# rev-polarity-deflector-dish-mk-2_0.net
KiCad netlist of a schematic drawn in EAGLE
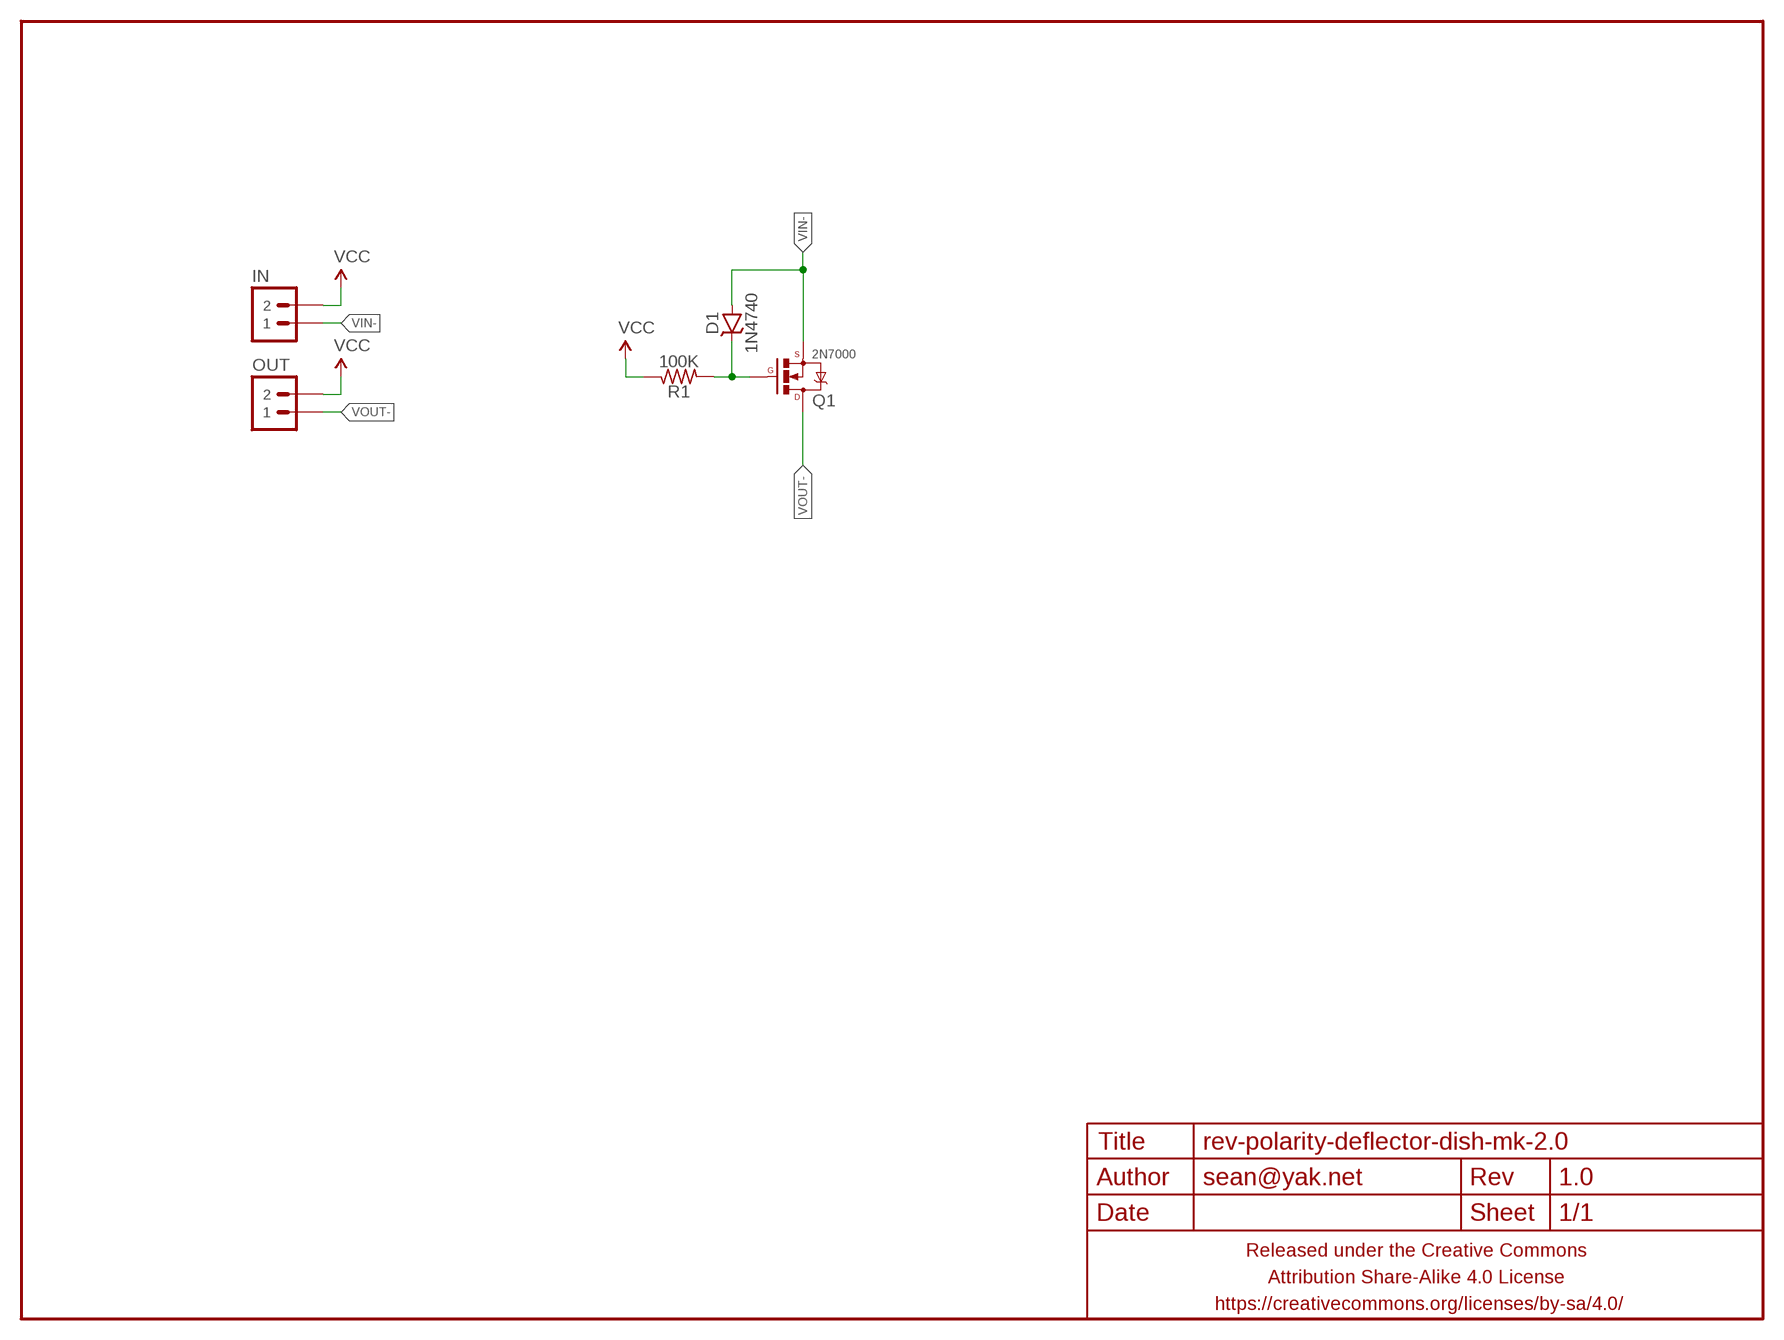
[diagram p0: schematic, sheet 1]

(export (version "E")
  (design (tool "Eeschema 10.0.6"))
  (components
    (comp (ref "D1")
      (value "1N4740")
      (footprint "eagle-import:SOT23")
      (libsource (lib "eagle-import") (part "DIODE-ZENERSOT23"))
    )
    (comp (ref "FRAME1")
      (value "FRAME-LETTERNO_PACKAGE")
      (footprint "eagle-import:DUMMY")
      (fields (field (name "DESIGNER") "sean@yak.net") (field (name "VERSION") "1.0"))
      (libsource (lib "eagle-import") (part "FRAME-LETTERNO_PACKAGE"))
    )
    (comp (ref "IN")
      (value "M02PTH-CENTERED")
      (footprint "eagle-import:1X02-CENTER")
      (libsource (lib "eagle-import") (part "M02PTH-CENTERED"))
    )
    (comp (ref "OUT")
      (value "M02PTH-CENTERED")
      (footprint "eagle-import:1X02-CENTER")
      (libsource (lib "eagle-import") (part "M02PTH-CENTERED"))
    )
    (comp (ref "Q1")
      (value "2N7000")
      (footprint "eagle-import:SOT23")
      (libsource (lib "eagle-import") (part "MOSFET-NCHANNELIRLML2502"))
    )
    (comp (ref "R1")
      (value "100K")
      (footprint "eagle-import:R0603")
      (libsource (lib "eagle-import") (part "RESISTORR0603"))
    )
  )
  (nets
    (net (code "1") (name "Net-(D1-C)") (class "Default")
      (node (ref "D1") (pin "3") (pinfunction "C_3") (pintype "passive"))
      (node (ref "Q1") (pin "1") (pinfunction "G_1") (pintype "passive"))
      (node (ref "R1") (pin "2") (pinfunction "2_2") (pintype "passive"))
    )
    (net (code "2") (name "VCC") (class "Default")
      (node (ref "IN") (pin "2") (pinfunction "2_2") (pintype "passive"))
      (node (ref "OUT") (pin "2") (pinfunction "2_2") (pintype "passive"))
      (node (ref "R1") (pin "1") (pinfunction "1_1") (pintype "passive"))
    )
    (net (code "3") (name "VIN-") (class "Default")
      (node (ref "D1") (pin "1") (pinfunction "A_1") (pintype "passive"))
      (node (ref "D1") (pin "2") (pinfunction "A_2") (pintype "passive"))
      (node (ref "IN") (pin "1") (pinfunction "1_1") (pintype "passive"))
      (node (ref "Q1") (pin "2") (pinfunction "S_2") (pintype "passive"))
    )
    (net (code "4") (name "VOUT-") (class "Default")
      (node (ref "OUT") (pin "1") (pinfunction "1_1") (pintype "passive"))
      (node (ref "Q1") (pin "3") (pinfunction "D_3") (pintype "passive"))
    )
  )
)
